# SingleToDifferential.net
KiCad netlist of a schematic drawn in Altium Designer
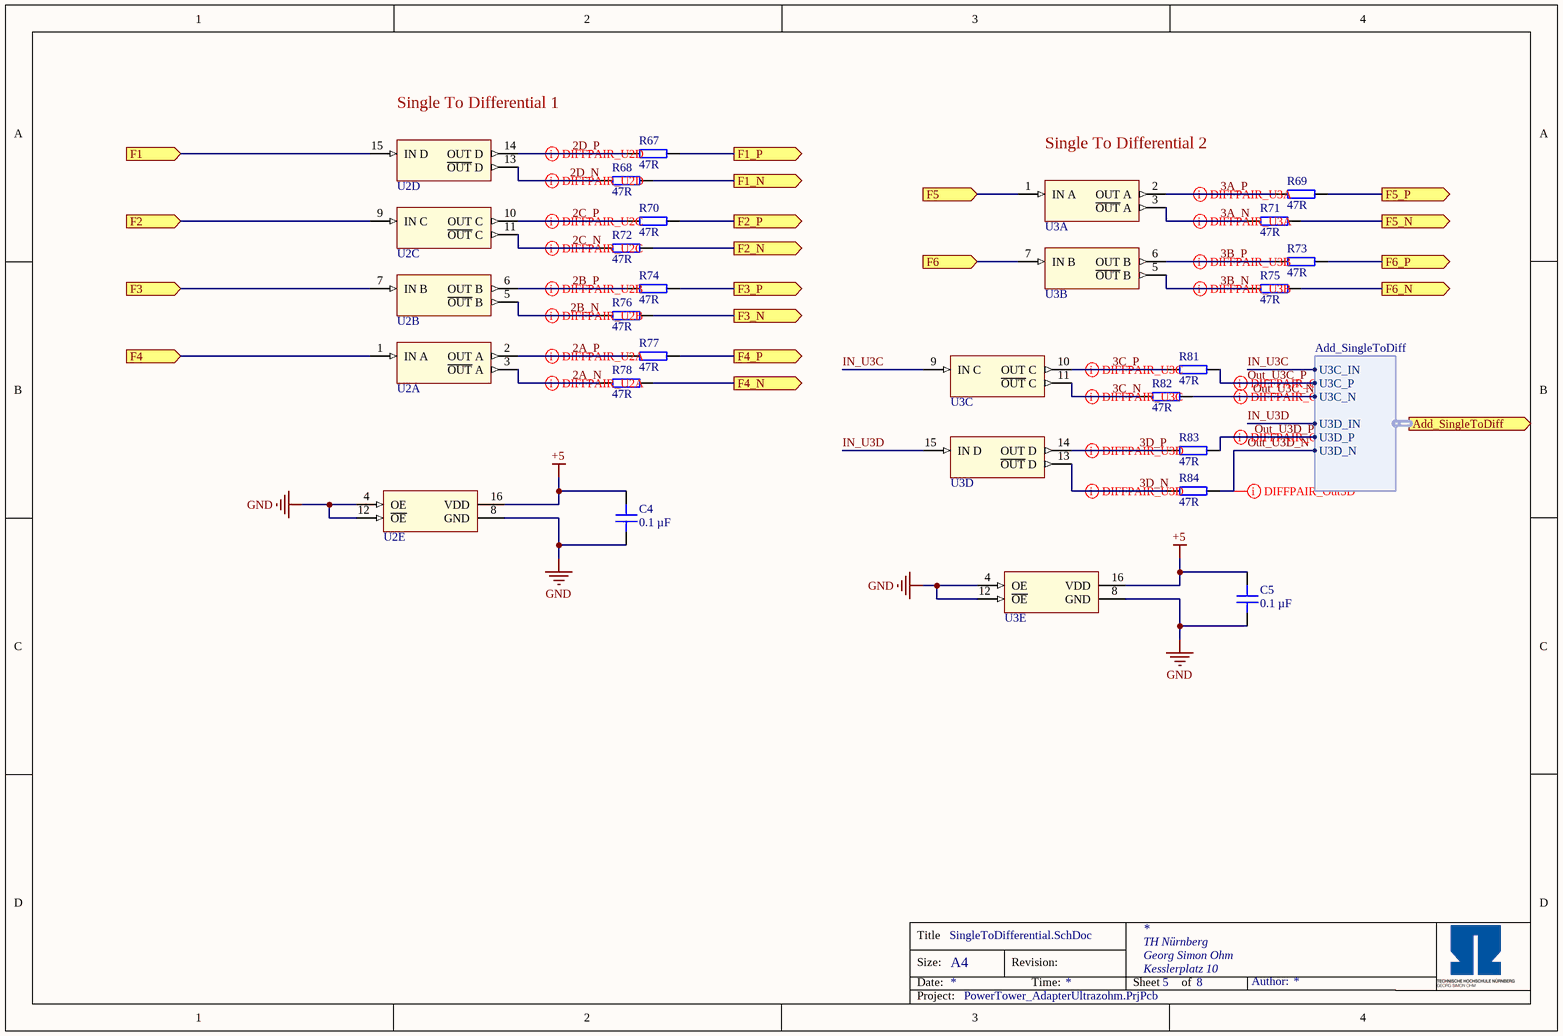
[diagram p0: SingleToDifferential.SchDoc]

(export (version "E")
  (design (tool "Eeschema 10.0.6"))
  (components
    (comp (ref "C4")
      (value "0.1 µF")
      (footprint "C_0603")
      (description "Capacitor 0603, 25 VDC, 0.1 µF, X7R")
      (fields
        (field (name "MANUFACTURER PART NUMBER") "C0603C104J3REC7411")
        (field (name "MANUFACTURER") "KEMET")
        (field (name "CREATED FROM") "MGremer")
      )
      (libsource (lib "user") (part "Capacitor"))
    )
    (comp (ref "C5")
      (value "0.1 µF")
      (footprint "C_0603")
      (description "Capacitor 0603, 25 VDC, 0.1 µF, X7R")
      (fields
        (field (name "MANUFACTURER PART NUMBER") "C0603C104J3REC7411")
        (field (name "MANUFACTURER") "KEMET")
        (field (name "CREATED FROM") "MGremer")
      )
      (libsource (lib "user") (part "Capacitor"))
    )
    (comp (ref "R67")
      (value "47R")
      (footprint "RES 0603_1608")
      (description "SMD resistor E24 series")
      (fields
        (field (name "MANUFACTURER PART NUMBER") "RK73B1JTTDD470J")
        (field (name "MANUFACTURER") "KOA Speer")
        (field (name "CREATED FROM") "MGremer")
      )
      (libsource (lib "user") (part "Resistor"))
    )
    (comp (ref "R68")
      (value "47R")
      (footprint "RES 0603_1608")
      (description "SMD resistor E24 series")
      (fields
        (field (name "MANUFACTURER PART NUMBER") "RK73B1JTTDD470J")
        (field (name "MANUFACTURER") "KOA Speer")
        (field (name "CREATED FROM") "MGremer")
      )
      (libsource (lib "user") (part "Resistor"))
    )
    (comp (ref "R69")
      (value "47R")
      (footprint "RES 0603_1608")
      (description "SMD resistor E24 series")
      (fields
        (field (name "MANUFACTURER PART NUMBER") "RK73B1JTTDD470J")
        (field (name "MANUFACTURER") "KOA Speer")
        (field (name "CREATED FROM") "MGremer")
      )
      (libsource (lib "user") (part "Resistor"))
    )
    (comp (ref "R70")
      (value "47R")
      (footprint "RES 0603_1608")
      (description "SMD resistor E24 series")
      (fields
        (field (name "MANUFACTURER PART NUMBER") "RK73B1JTTDD470J")
        (field (name "MANUFACTURER") "KOA Speer")
        (field (name "CREATED FROM") "MGremer")
      )
      (libsource (lib "user") (part "Resistor"))
    )
    (comp (ref "R71")
      (value "47R")
      (footprint "RES 0603_1608")
      (description "SMD resistor E24 series")
      (fields
        (field (name "MANUFACTURER PART NUMBER") "RK73B1JTTDD470J")
        (field (name "MANUFACTURER") "KOA Speer")
        (field (name "CREATED FROM") "MGremer")
      )
      (libsource (lib "user") (part "Resistor"))
    )
    (comp (ref "R72")
      (value "47R")
      (footprint "RES 0603_1608")
      (description "SMD resistor E24 series")
      (fields
        (field (name "MANUFACTURER PART NUMBER") "RK73B1JTTDD470J")
        (field (name "MANUFACTURER") "KOA Speer")
        (field (name "CREATED FROM") "MGremer")
      )
      (libsource (lib "user") (part "Resistor"))
    )
    (comp (ref "R73")
      (value "47R")
      (footprint "RES 0603_1608")
      (description "SMD resistor E24 series")
      (fields
        (field (name "MANUFACTURER PART NUMBER") "RK73B1JTTDD470J")
        (field (name "MANUFACTURER") "KOA Speer")
        (field (name "CREATED FROM") "MGremer")
      )
      (libsource (lib "user") (part "Resistor"))
    )
    (comp (ref "R74")
      (value "47R")
      (footprint "RES 0603_1608")
      (description "SMD resistor E24 series")
      (fields
        (field (name "MANUFACTURER PART NUMBER") "RK73B1JTTDD470J")
        (field (name "MANUFACTURER") "KOA Speer")
        (field (name "CREATED FROM") "MGremer")
      )
      (libsource (lib "user") (part "Resistor"))
    )
    (comp (ref "R75")
      (value "47R")
      (footprint "RES 0603_1608")
      (description "SMD resistor E24 series")
      (fields
        (field (name "MANUFACTURER PART NUMBER") "RK73B1JTTDD470J")
        (field (name "MANUFACTURER") "KOA Speer")
        (field (name "CREATED FROM") "MGremer")
      )
      (libsource (lib "user") (part "Resistor"))
    )
    (comp (ref "R76")
      (value "47R")
      (footprint "RES 0603_1608")
      (description "SMD resistor E24 series")
      (fields
        (field (name "MANUFACTURER PART NUMBER") "RK73B1JTTDD470J")
        (field (name "MANUFACTURER") "KOA Speer")
        (field (name "CREATED FROM") "MGremer")
      )
      (libsource (lib "user") (part "Resistor"))
    )
    (comp (ref "R77")
      (value "47R")
      (footprint "RES 0603_1608")
      (description "SMD resistor E24 series")
      (fields
        (field (name "MANUFACTURER PART NUMBER") "RK73B1JTTDD470J")
        (field (name "MANUFACTURER") "KOA Speer")
        (field (name "CREATED FROM") "MGremer")
      )
      (libsource (lib "user") (part "Resistor"))
    )
    (comp (ref "R78")
      (value "47R")
      (footprint "RES 0603_1608")
      (description "SMD resistor E24 series")
      (fields
        (field (name "MANUFACTURER PART NUMBER") "RK73B1JTTDD470J")
        (field (name "MANUFACTURER") "KOA Speer")
        (field (name "CREATED FROM") "MGremer")
      )
      (libsource (lib "user") (part "Resistor"))
    )
    (comp (ref "R81")
      (value "47R")
      (footprint "RES 0603_1608")
      (description "SMD resistor E24 series")
      (fields
        (field (name "MANUFACTURER PART NUMBER") "RK73B1JTTDD470J")
        (field (name "MANUFACTURER") "KOA Speer")
        (field (name "CREATED FROM") "MGremer")
      )
      (libsource (lib "user") (part "Resistor"))
    )
    (comp (ref "R82")
      (value "47R")
      (footprint "RES 0603_1608")
      (description "SMD resistor E24 series")
      (fields
        (field (name "MANUFACTURER PART NUMBER") "RK73B1JTTDD470J")
        (field (name "MANUFACTURER") "KOA Speer")
        (field (name "CREATED FROM") "MGremer")
      )
      (libsource (lib "user") (part "Resistor"))
    )
    (comp (ref "R83")
      (value "47R")
      (footprint "RES 0603_1608")
      (description "SMD resistor E24 series")
      (fields
        (field (name "MANUFACTURER PART NUMBER") "RK73B1JTTDD470J")
        (field (name "MANUFACTURER") "KOA Speer")
        (field (name "CREATED FROM") "MGremer")
      )
      (libsource (lib "user") (part "Resistor"))
    )
    (comp (ref "R84")
      (value "47R")
      (footprint "RES 0603_1608")
      (description "SMD resistor E24 series")
      (fields
        (field (name "MANUFACTURER PART NUMBER") "RK73B1JTTDD470J")
        (field (name "MANUFACTURER") "KOA Speer")
        (field (name "CREATED FROM") "MGremer")
      )
      (libsource (lib "user") (part "Resistor"))
    )
    (comp (ref "U2")
      (value "DS26C31TMX/NOPB")
      (footprint "TI_D-R-PDSO-G16_N")
      (description "CMOS Quad Tri-State Differential Line Drivers, 16-pin Narrow SOIC, Pb-Free")
      (fields
        (field (name "MANUFACTURER") "Texas Instruments")
        (field (name "LCSC PART NUMBER") "C132085")
        (field (name "CREATED FROM") "T. Wendt")
      )
      (libsource (lib "user") (part "DS26C31TMX"))
    )
    (comp (ref "U3")
      (value "DS26C31TMX/NOPB")
      (footprint "TI_D-R-PDSO-G16_N")
      (description "CMOS Quad Tri-State Differential Line Drivers, 16-pin Narrow SOIC, Pb-Free")
      (fields
        (field (name "MANUFACTURER") "Texas Instruments")
        (field (name "LCSC PART NUMBER") "C132085")
        (field (name "CREATED FROM") "T. Wendt")
      )
      (libsource (lib "user") (part "DS26C31TMX"))
    )
  )
  (nets
    (net (code "2") (name "+5") (class "Default")
      (node (ref "C4") (pin "2") (pinfunction "2_2") (pintype "passive"))
      (node (ref "C5") (pin "2") (pinfunction "2_2") (pintype "passive"))
      (node (ref "U2") (pin "16") (pinfunction "VDD_16") (pintype "power_in"))
      (node (ref "U3") (pin "16") (pinfunction "VDD_16") (pintype "power_in"))
    )
    (net (code "3") (name "/2A_N") (class "Default")
      (node (ref "R78") (pin "1") (pinfunction "1_1") (pintype "passive"))
      (node (ref "U2") (pin "3") (pinfunction "~{OUT}_A_3") (pintype "output"))
    )
    (net (code "4") (name "/2A_P") (class "Default")
      (node (ref "R77") (pin "1") (pinfunction "1_1") (pintype "passive"))
      (node (ref "U2") (pin "2") (pinfunction "OUT_A_2") (pintype "output"))
    )
    (net (code "5") (name "/2B_N") (class "Default")
      (node (ref "R76") (pin "1") (pinfunction "1_1") (pintype "passive"))
      (node (ref "U2") (pin "5") (pinfunction "~{OUT}_B_5") (pintype "output"))
    )
    (net (code "6") (name "/2B_P") (class "Default")
      (node (ref "R74") (pin "1") (pinfunction "1_1") (pintype "passive"))
      (node (ref "U2") (pin "6") (pinfunction "OUT_B_6") (pintype "output"))
    )
    (net (code "7") (name "/2C_N") (class "Default")
      (node (ref "R72") (pin "1") (pinfunction "1_1") (pintype "passive"))
      (node (ref "U2") (pin "11") (pinfunction "~{OUT}_C_11") (pintype "output"))
    )
    (net (code "8") (name "/2C_P") (class "Default")
      (node (ref "R70") (pin "1") (pinfunction "1_1") (pintype "passive"))
      (node (ref "U2") (pin "10") (pinfunction "OUT_C_10") (pintype "output"))
    )
    (net (code "9") (name "/2D_N") (class "Default")
      (node (ref "R68") (pin "1") (pinfunction "1_1") (pintype "passive"))
      (node (ref "U2") (pin "13") (pinfunction "~{OUT}_D_13") (pintype "output"))
    )
    (net (code "10") (name "/2D_P") (class "Default")
      (node (ref "R67") (pin "1") (pinfunction "1_1") (pintype "passive"))
      (node (ref "U2") (pin "14") (pinfunction "OUT_D_14") (pintype "output"))
    )
    (net (code "11") (name "/3A_N") (class "Default")
      (node (ref "R71") (pin "1") (pinfunction "1_1") (pintype "passive"))
      (node (ref "U3") (pin "3") (pinfunction "~{OUT}_A_3") (pintype "output"))
    )
    (net (code "12") (name "/3A_P") (class "Default")
      (node (ref "R69") (pin "1") (pinfunction "1_1") (pintype "passive"))
      (node (ref "U3") (pin "2") (pinfunction "OUT_A_2") (pintype "output"))
    )
    (net (code "13") (name "/3B_N") (class "Default")
      (node (ref "R75") (pin "1") (pinfunction "1_1") (pintype "passive"))
      (node (ref "U3") (pin "5") (pinfunction "~{OUT}_B_5") (pintype "output"))
    )
    (net (code "14") (name "/3B_P") (class "Default")
      (node (ref "R73") (pin "1") (pinfunction "1_1") (pintype "passive"))
      (node (ref "U3") (pin "6") (pinfunction "OUT_B_6") (pintype "output"))
    )
    (net (code "15") (name "/3C_N") (class "Default")
      (node (ref "R82") (pin "1") (pinfunction "1_1") (pintype "passive"))
      (node (ref "U3") (pin "11") (pinfunction "~{OUT}_C_11") (pintype "output"))
    )
    (net (code "16") (name "/3C_P") (class "Default")
      (node (ref "R81") (pin "1") (pinfunction "1_1") (pintype "passive"))
      (node (ref "U3") (pin "10") (pinfunction "OUT_C_10") (pintype "output"))
    )
    (net (code "17") (name "/3D_N") (class "Default")
      (node (ref "R84") (pin "1") (pinfunction "1_1") (pintype "passive"))
      (node (ref "U3") (pin "13") (pinfunction "~{OUT}_D_13") (pintype "output"))
    )
    (net (code "18") (name "/3D_P") (class "Default")
      (node (ref "R83") (pin "1") (pinfunction "1_1") (pintype "passive"))
      (node (ref "U3") (pin "14") (pinfunction "OUT_D_14") (pintype "output"))
    )
    (net (code "19") (name "/F1") (class "Default")
      (node (ref "U2") (pin "15") (pinfunction "IN_D_15") (pintype "input"))
    )
    (net (code "20") (name "/F1_N") (class "Default")
      (node (ref "R68") (pin "2") (pinfunction "2_2") (pintype "passive"))
    )
    (net (code "21") (name "/F1_P") (class "Default")
      (node (ref "R67") (pin "2") (pinfunction "2_2") (pintype "passive"))
    )
    (net (code "22") (name "/F2") (class "Default")
      (node (ref "U2") (pin "9") (pinfunction "IN_C_9") (pintype "input"))
    )
    (net (code "23") (name "/F2_N") (class "Default")
      (node (ref "R72") (pin "2") (pinfunction "2_2") (pintype "passive"))
    )
    (net (code "24") (name "/F2_P") (class "Default")
      (node (ref "R70") (pin "2") (pinfunction "2_2") (pintype "passive"))
    )
    (net (code "25") (name "/F3") (class "Default")
      (node (ref "U2") (pin "7") (pinfunction "IN_B_7") (pintype "input"))
    )
    (net (code "26") (name "/F3_N") (class "Default")
      (node (ref "R76") (pin "2") (pinfunction "2_2") (pintype "passive"))
    )
    (net (code "27") (name "/F3_P") (class "Default")
      (node (ref "R74") (pin "2") (pinfunction "2_2") (pintype "passive"))
    )
    (net (code "28") (name "/F4") (class "Default")
      (node (ref "U2") (pin "1") (pinfunction "IN_A_1") (pintype "input"))
    )
    (net (code "29") (name "/F4_N") (class "Default")
      (node (ref "R78") (pin "2") (pinfunction "2_2") (pintype "passive"))
    )
    (net (code "30") (name "/F4_P") (class "Default")
      (node (ref "R77") (pin "2") (pinfunction "2_2") (pintype "passive"))
    )
    (net (code "31") (name "/F5") (class "Default")
      (node (ref "U3") (pin "1") (pinfunction "IN_A_1") (pintype "input"))
    )
    (net (code "32") (name "/F5_N") (class "Default")
      (node (ref "R71") (pin "2") (pinfunction "2_2") (pintype "passive"))
    )
    (net (code "33") (name "/F5_P") (class "Default")
      (node (ref "R69") (pin "2") (pinfunction "2_2") (pintype "passive"))
    )
    (net (code "34") (name "/F6") (class "Default")
      (node (ref "U3") (pin "7") (pinfunction "IN_B_7") (pintype "input"))
    )
    (net (code "35") (name "/F6_N") (class "Default")
      (node (ref "R75") (pin "2") (pinfunction "2_2") (pintype "passive"))
    )
    (net (code "36") (name "/F6_P") (class "Default")
      (node (ref "R73") (pin "2") (pinfunction "2_2") (pintype "passive"))
    )
    (net (code "37") (name "/IN_U3C") (class "Default")
      (node (ref "U3") (pin "9") (pinfunction "IN_C_9") (pintype "input"))
    )
    (net (code "38") (name "/IN_U3D") (class "Default")
      (node (ref "U3") (pin "15") (pinfunction "IN_D_15") (pintype "input"))
    )
    (net (code "39") (name "/Out_U3C_N") (class "Default")
      (node (ref "R82") (pin "2") (pinfunction "2_2") (pintype "passive"))
    )
    (net (code "40") (name "/Out_U3C_P") (class "Default")
      (node (ref "R81") (pin "2") (pinfunction "2_2") (pintype "passive"))
    )
    (net (code "41") (name "/Out_U3D_N") (class "Default")
      (node (ref "R84") (pin "2") (pinfunction "2_2") (pintype "passive"))
    )
    (net (code "42") (name "/Out_U3D_P") (class "Default")
      (node (ref "R83") (pin "2") (pinfunction "2_2") (pintype "passive"))
    )
    (net (code "44") (name "GND") (class "Default")
      (node (ref "C4") (pin "1") (pinfunction "1_1") (pintype "passive"))
      (node (ref "C5") (pin "1") (pinfunction "1_1") (pintype "passive"))
      (node (ref "U2") (pin "12") (pinfunction "~{OE}_12") (pintype "input"))
      (node (ref "U2") (pin "4") (pinfunction "OE_4") (pintype "input"))
      (node (ref "U2") (pin "8") (pinfunction "GND_8") (pintype "power_in"))
      (node (ref "U3") (pin "12") (pinfunction "~{OE}_12") (pintype "input"))
      (node (ref "U3") (pin "4") (pinfunction "OE_4") (pintype "input"))
      (node (ref "U3") (pin "8") (pinfunction "GND_8") (pintype "power_in"))
    )
  )
)
